# R151B.net
KiCad netlist of a schematic drawn in EAGLE
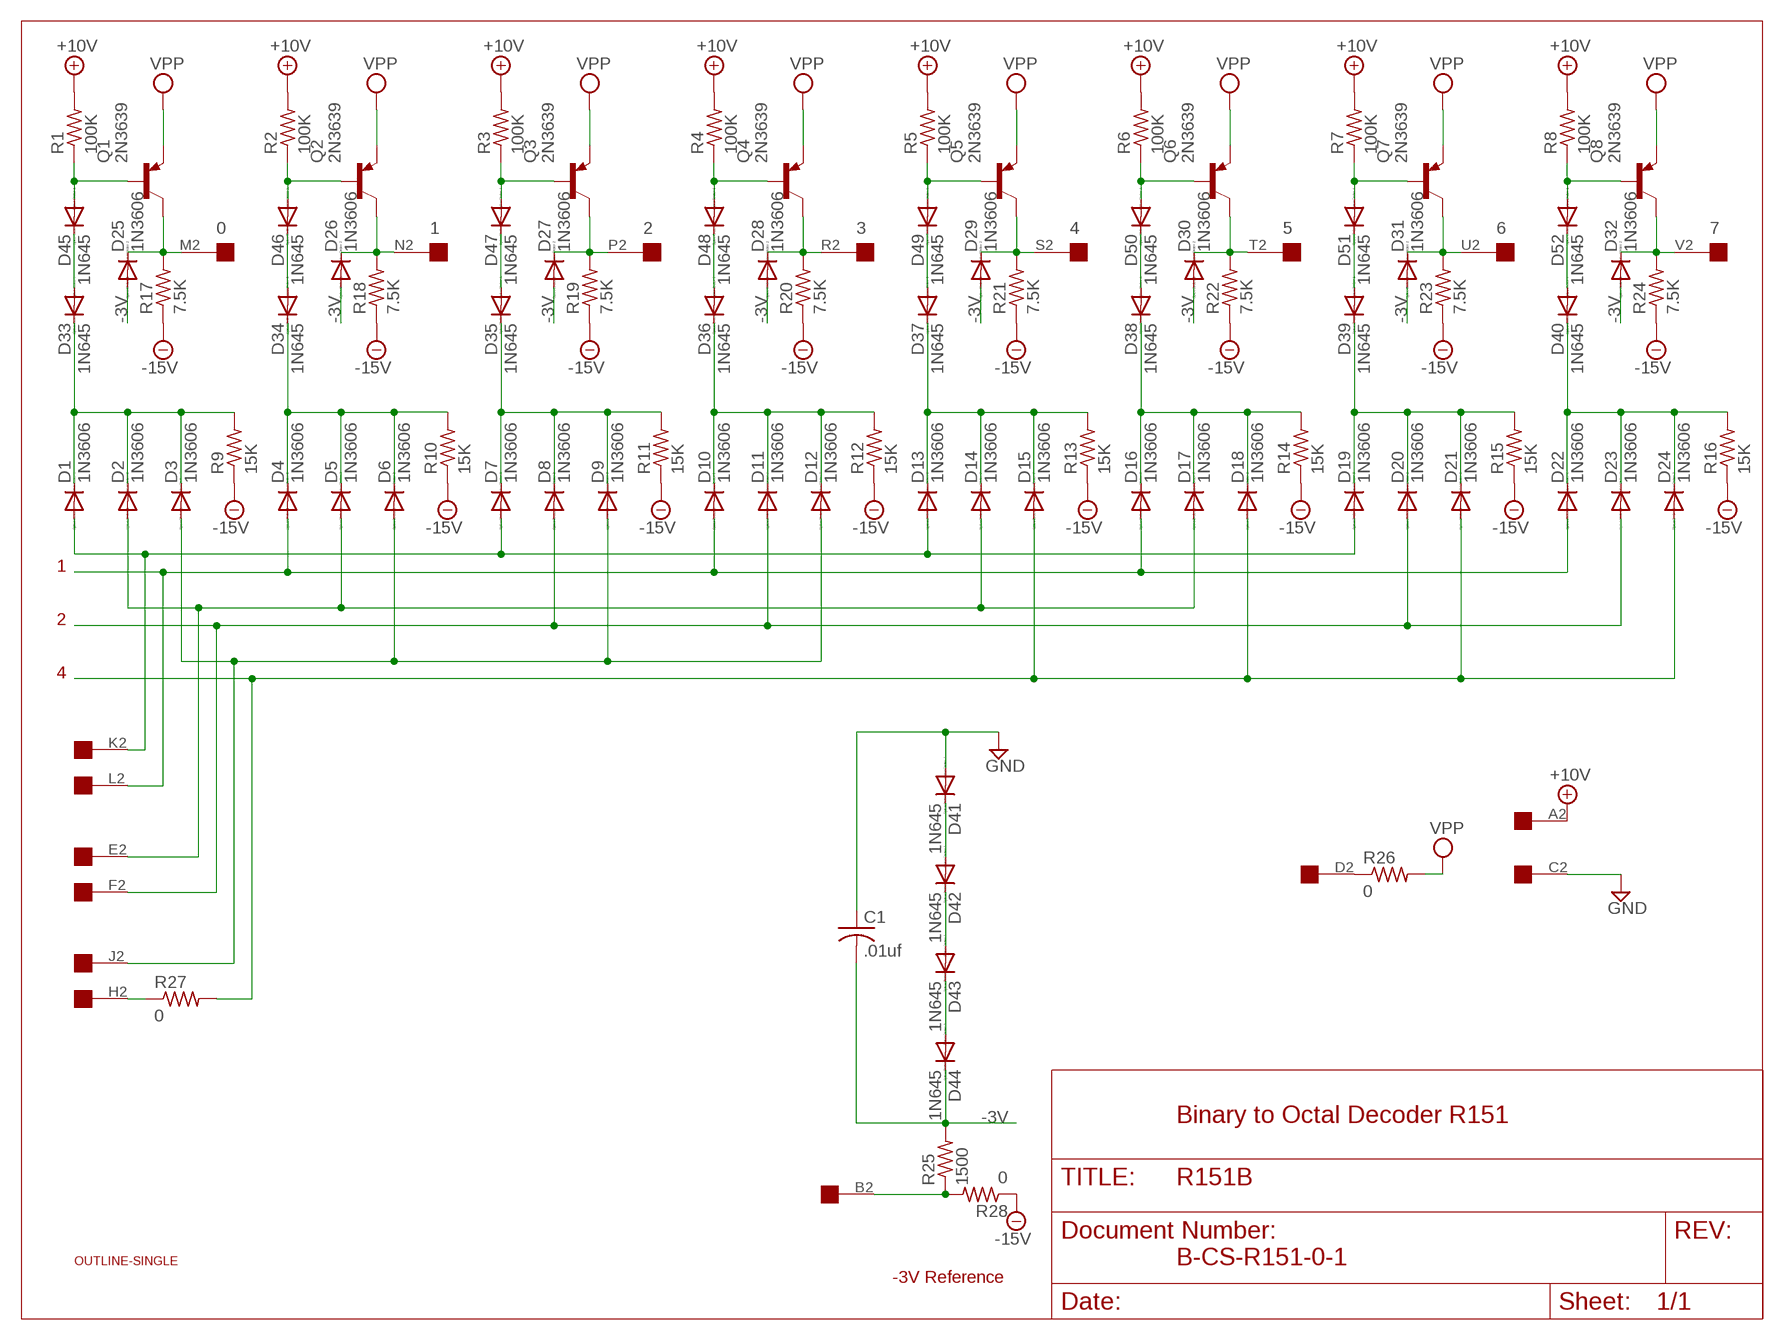
[diagram p0: schematic, sheet 1]

(export (version "E")
  (design (tool "Eeschema 10.0.6"))
  (components
    (comp (ref "C1")
      (value ".01uf")
      (footprint "eagle-import:C050-025X075")
      (libsource (lib "eagle-import") (part "C-US050-025X075"))
    )
    (comp (ref "D1")
      (value "1N3606")
      (footprint "eagle-import:DO35-10")
      (libsource (lib "eagle-import") (part "1N4148DO35-10"))
    )
    (comp (ref "D2")
      (value "1N3606")
      (footprint "eagle-import:DO35-10")
      (libsource (lib "eagle-import") (part "1N4148DO35-10"))
    )
    (comp (ref "D3")
      (value "1N3606")
      (footprint "eagle-import:DO35-10")
      (libsource (lib "eagle-import") (part "1N4148DO35-10"))
    )
    (comp (ref "D4")
      (value "1N3606")
      (footprint "eagle-import:DO35-10")
      (libsource (lib "eagle-import") (part "1N4148DO35-10"))
    )
    (comp (ref "D5")
      (value "1N3606")
      (footprint "eagle-import:DO35-10")
      (libsource (lib "eagle-import") (part "1N4148DO35-10"))
    )
    (comp (ref "D6")
      (value "1N3606")
      (footprint "eagle-import:DO35-10")
      (libsource (lib "eagle-import") (part "1N4148DO35-10"))
    )
    (comp (ref "D7")
      (value "1N3606")
      (footprint "eagle-import:DO35-10")
      (libsource (lib "eagle-import") (part "1N4148DO35-10"))
    )
    (comp (ref "D8")
      (value "1N3606")
      (footprint "eagle-import:DO35-10")
      (libsource (lib "eagle-import") (part "1N4148DO35-10"))
    )
    (comp (ref "D9")
      (value "1N3606")
      (footprint "eagle-import:DO35-10")
      (libsource (lib "eagle-import") (part "1N4148DO35-10"))
    )
    (comp (ref "D10")
      (value "1N3606")
      (footprint "eagle-import:DO35-10")
      (libsource (lib "eagle-import") (part "1N4148DO35-10"))
    )
    (comp (ref "D11")
      (value "1N3606")
      (footprint "eagle-import:DO35-10")
      (libsource (lib "eagle-import") (part "1N4148DO35-10"))
    )
    (comp (ref "D12")
      (value "1N3606")
      (footprint "eagle-import:DO35-10")
      (libsource (lib "eagle-import") (part "1N4148DO35-10"))
    )
    (comp (ref "D13")
      (value "1N3606")
      (footprint "eagle-import:DO35-10")
      (libsource (lib "eagle-import") (part "1N4148DO35-10"))
    )
    (comp (ref "D14")
      (value "1N3606")
      (footprint "eagle-import:DO35-10")
      (libsource (lib "eagle-import") (part "1N4148DO35-10"))
    )
    (comp (ref "D15")
      (value "1N3606")
      (footprint "eagle-import:DO35-10")
      (libsource (lib "eagle-import") (part "1N4148DO35-10"))
    )
    (comp (ref "D16")
      (value "1N3606")
      (footprint "eagle-import:DO35-10")
      (libsource (lib "eagle-import") (part "1N4148DO35-10"))
    )
    (comp (ref "D17")
      (value "1N3606")
      (footprint "eagle-import:DO35-10")
      (libsource (lib "eagle-import") (part "1N4148DO35-10"))
    )
    (comp (ref "D18")
      (value "1N3606")
      (footprint "eagle-import:DO35-10")
      (libsource (lib "eagle-import") (part "1N4148DO35-10"))
    )
    (comp (ref "D19")
      (value "1N3606")
      (footprint "eagle-import:DO35-10")
      (libsource (lib "eagle-import") (part "1N4148DO35-10"))
    )
    (comp (ref "D20")
      (value "1N3606")
      (footprint "eagle-import:DO35-10")
      (libsource (lib "eagle-import") (part "1N4148DO35-10"))
    )
    (comp (ref "D21")
      (value "1N3606")
      (footprint "eagle-import:DO35-10")
      (libsource (lib "eagle-import") (part "1N4148DO35-10"))
    )
    (comp (ref "D22")
      (value "1N3606")
      (footprint "eagle-import:DO35-10")
      (libsource (lib "eagle-import") (part "1N4148DO35-10"))
    )
    (comp (ref "D23")
      (value "1N3606")
      (footprint "eagle-import:DO35-10")
      (libsource (lib "eagle-import") (part "1N4148DO35-10"))
    )
    (comp (ref "D24")
      (value "1N3606")
      (footprint "eagle-import:DO35-10")
      (libsource (lib "eagle-import") (part "1N4148DO35-10"))
    )
    (comp (ref "D25")
      (value "1N3606")
      (footprint "eagle-import:DO35-10")
      (libsource (lib "eagle-import") (part "1N4148DO35-10"))
    )
    (comp (ref "D26")
      (value "1N3606")
      (footprint "eagle-import:DO35-10")
      (libsource (lib "eagle-import") (part "1N4148DO35-10"))
    )
    (comp (ref "D27")
      (value "1N3606")
      (footprint "eagle-import:DO35-10")
      (libsource (lib "eagle-import") (part "1N4148DO35-10"))
    )
    (comp (ref "D28")
      (value "1N3606")
      (footprint "eagle-import:DO35-10")
      (libsource (lib "eagle-import") (part "1N4148DO35-10"))
    )
    (comp (ref "D29")
      (value "1N3606")
      (footprint "eagle-import:DO35-10")
      (libsource (lib "eagle-import") (part "1N4148DO35-10"))
    )
    (comp (ref "D30")
      (value "1N3606")
      (footprint "eagle-import:DO35-10")
      (libsource (lib "eagle-import") (part "1N4148DO35-10"))
    )
    (comp (ref "D31")
      (value "1N3606")
      (footprint "eagle-import:DO35-10")
      (libsource (lib "eagle-import") (part "1N4148DO35-10"))
    )
    (comp (ref "D32")
      (value "1N3606")
      (footprint "eagle-import:DO35-10")
      (libsource (lib "eagle-import") (part "1N4148DO35-10"))
    )
    (comp (ref "D33")
      (value "1N645")
      (footprint "eagle-import:DO35-10")
      (libsource (lib "eagle-import") (part "1N4148DO35-10"))
    )
    (comp (ref "D34")
      (value "1N645")
      (footprint "eagle-import:DO35-10")
      (libsource (lib "eagle-import") (part "1N4148DO35-10"))
    )
    (comp (ref "D35")
      (value "1N645")
      (footprint "eagle-import:DO35-10")
      (libsource (lib "eagle-import") (part "1N4148DO35-10"))
    )
    (comp (ref "D36")
      (value "1N645")
      (footprint "eagle-import:DO35-10")
      (libsource (lib "eagle-import") (part "1N4148DO35-10"))
    )
    (comp (ref "D37")
      (value "1N645")
      (footprint "eagle-import:DO35-10")
      (libsource (lib "eagle-import") (part "1N4148DO35-10"))
    )
    (comp (ref "D38")
      (value "1N645")
      (footprint "eagle-import:DO35-10")
      (libsource (lib "eagle-import") (part "1N4148DO35-10"))
    )
    (comp (ref "D39")
      (value "1N645")
      (footprint "eagle-import:DO35-10")
      (libsource (lib "eagle-import") (part "1N4148DO35-10"))
    )
    (comp (ref "D40")
      (value "1N645")
      (footprint "eagle-import:DO35-10")
      (libsource (lib "eagle-import") (part "1N4148DO35-10"))
    )
    (comp (ref "D41")
      (value "1N645")
      (footprint "eagle-import:DO35-10")
      (libsource (lib "eagle-import") (part "1N4148DO35-10"))
    )
    (comp (ref "D42")
      (value "1N645")
      (footprint "eagle-import:DO35-10")
      (libsource (lib "eagle-import") (part "1N4148DO35-10"))
    )
    (comp (ref "D43")
      (value "1N645")
      (footprint "eagle-import:DO35-10")
      (libsource (lib "eagle-import") (part "1N4148DO35-10"))
    )
    (comp (ref "D44")
      (value "1N645")
      (footprint "eagle-import:DO35-10")
      (libsource (lib "eagle-import") (part "1N4148DO35-10"))
    )
    (comp (ref "D45")
      (value "1N645")
      (footprint "eagle-import:DO35-10")
      (libsource (lib "eagle-import") (part "1N4148DO35-10"))
    )
    (comp (ref "D46")
      (value "1N645")
      (footprint "eagle-import:DO35-10")
      (libsource (lib "eagle-import") (part "1N4148DO35-10"))
    )
    (comp (ref "D47")
      (value "1N645")
      (footprint "eagle-import:DO35-10")
      (libsource (lib "eagle-import") (part "1N4148DO35-10"))
    )
    (comp (ref "D48")
      (value "1N645")
      (footprint "eagle-import:DO35-10")
      (libsource (lib "eagle-import") (part "1N4148DO35-10"))
    )
    (comp (ref "D49")
      (value "1N645")
      (footprint "eagle-import:DO35-10")
      (libsource (lib "eagle-import") (part "1N4148DO35-10"))
    )
    (comp (ref "D50")
      (value "1N645")
      (footprint "eagle-import:DO35-10")
      (libsource (lib "eagle-import") (part "1N4148DO35-10"))
    )
    (comp (ref "D51")
      (value "1N645")
      (footprint "eagle-import:DO35-10")
      (libsource (lib "eagle-import") (part "1N4148DO35-10"))
    )
    (comp (ref "D52")
      (value "1N645")
      (footprint "eagle-import:DO35-10")
      (libsource (lib "eagle-import") (part "1N4148DO35-10"))
    )
    (comp (ref "Q1")
      (value "2N3639")
      (footprint "eagle-import:TO39")
      (libsource (lib "eagle-import") (part "2N3637"))
    )
    (comp (ref "Q2")
      (value "2N3639")
      (footprint "eagle-import:TO39")
      (libsource (lib "eagle-import") (part "2N3637"))
    )
    (comp (ref "Q3")
      (value "2N3639")
      (footprint "eagle-import:TO39")
      (libsource (lib "eagle-import") (part "2N3637"))
    )
    (comp (ref "Q4")
      (value "2N3639")
      (footprint "eagle-import:TO39")
      (libsource (lib "eagle-import") (part "2N3637"))
    )
    (comp (ref "Q5")
      (value "2N3639")
      (footprint "eagle-import:TO39")
      (libsource (lib "eagle-import") (part "2N3637"))
    )
    (comp (ref "Q6")
      (value "2N3639")
      (footprint "eagle-import:TO39")
      (libsource (lib "eagle-import") (part "2N3637"))
    )
    (comp (ref "Q7")
      (value "2N3639")
      (footprint "eagle-import:TO39")
      (libsource (lib "eagle-import") (part "2N3637"))
    )
    (comp (ref "Q8")
      (value "2N3639")
      (footprint "eagle-import:TO39")
      (libsource (lib "eagle-import") (part "2N3637"))
    )
    (comp (ref "R1")
      (value "100K")
      (footprint "eagle-import:0207_10")
      (libsource (lib "eagle-import") (part "R-US_0207/10"))
    )
    (comp (ref "R2")
      (value "100K")
      (footprint "eagle-import:0207_10")
      (libsource (lib "eagle-import") (part "R-US_0207/10"))
    )
    (comp (ref "R3")
      (value "100K")
      (footprint "eagle-import:0207_10")
      (libsource (lib "eagle-import") (part "R-US_0207/10"))
    )
    (comp (ref "R4")
      (value "100K")
      (footprint "eagle-import:0207_10")
      (libsource (lib "eagle-import") (part "R-US_0207/10"))
    )
    (comp (ref "R5")
      (value "100K")
      (footprint "eagle-import:0207_10")
      (libsource (lib "eagle-import") (part "R-US_0207/10"))
    )
    (comp (ref "R6")
      (value "100K")
      (footprint "eagle-import:0207_10")
      (libsource (lib "eagle-import") (part "R-US_0207/10"))
    )
    (comp (ref "R7")
      (value "100K")
      (footprint "eagle-import:0207_10")
      (libsource (lib "eagle-import") (part "R-US_0207/10"))
    )
    (comp (ref "R8")
      (value "100K")
      (footprint "eagle-import:0207_10")
      (libsource (lib "eagle-import") (part "R-US_0207/10"))
    )
    (comp (ref "R9")
      (value "15K")
      (footprint "eagle-import:0207_10")
      (libsource (lib "eagle-import") (part "R-US_0207/10"))
    )
    (comp (ref "R10")
      (value "15K")
      (footprint "eagle-import:0207_10")
      (libsource (lib "eagle-import") (part "R-US_0207/10"))
    )
    (comp (ref "R11")
      (value "15K")
      (footprint "eagle-import:0207_10")
      (libsource (lib "eagle-import") (part "R-US_0207/10"))
    )
    (comp (ref "R12")
      (value "15K")
      (footprint "eagle-import:0207_10")
      (libsource (lib "eagle-import") (part "R-US_0207/10"))
    )
    (comp (ref "R13")
      (value "15K")
      (footprint "eagle-import:0207_10")
      (libsource (lib "eagle-import") (part "R-US_0207/10"))
    )
    (comp (ref "R14")
      (value "15K")
      (footprint "eagle-import:0207_10")
      (libsource (lib "eagle-import") (part "R-US_0207/10"))
    )
    (comp (ref "R15")
      (value "15K")
      (footprint "eagle-import:0207_10")
      (libsource (lib "eagle-import") (part "R-US_0207/10"))
    )
    (comp (ref "R16")
      (value "15K")
      (footprint "eagle-import:0207_10")
      (libsource (lib "eagle-import") (part "R-US_0207/10"))
    )
    (comp (ref "R17")
      (value "7.5K")
      (footprint "eagle-import:0207_10")
      (libsource (lib "eagle-import") (part "R-US_0207/10"))
    )
    (comp (ref "R18")
      (value "7.5K")
      (footprint "eagle-import:0207_10")
      (libsource (lib "eagle-import") (part "R-US_0207/10"))
    )
    (comp (ref "R19")
      (value "7.5K")
      (footprint "eagle-import:0207_10")
      (libsource (lib "eagle-import") (part "R-US_0207/10"))
    )
    (comp (ref "R20")
      (value "7.5K")
      (footprint "eagle-import:0207_10")
      (libsource (lib "eagle-import") (part "R-US_0207/10"))
    )
    (comp (ref "R21")
      (value "7.5K")
      (footprint "eagle-import:0207_10")
      (libsource (lib "eagle-import") (part "R-US_0207/10"))
    )
    (comp (ref "R22")
      (value "7.5K")
      (footprint "eagle-import:0207_10")
      (libsource (lib "eagle-import") (part "R-US_0207/10"))
    )
    (comp (ref "R23")
      (value "7.5K")
      (footprint "eagle-import:0207_10")
      (libsource (lib "eagle-import") (part "R-US_0207/10"))
    )
    (comp (ref "R24")
      (value "7.5K")
      (footprint "eagle-import:0207_10")
      (libsource (lib "eagle-import") (part "R-US_0207/10"))
    )
    (comp (ref "R25")
      (value "1500")
      (footprint "eagle-import:0207_10")
      (libsource (lib "eagle-import") (part "R-US_0207/10"))
    )
    (comp (ref "R26")
      (value "0")
      (footprint "eagle-import:0207_10")
      (libsource (lib "eagle-import") (part "R-US_0207/10"))
    )
    (comp (ref "R27")
      (value "0")
      (footprint "eagle-import:0207_10")
      (libsource (lib "eagle-import") (part "R-US_0207/10"))
    )
    (comp (ref "R28")
      (value "0")
      (footprint "eagle-import:0207_10")
      (libsource (lib "eagle-import") (part "R-US_0207/10"))
    )
    (comp (ref "U$1")
      (value "OUTLINE-SINGLE")
      (footprint "eagle-import:SINGLE")
      (libsource (lib "eagle-import") (part "OUTLINE-SINGLE"))
    )
    (comp (ref "U$2")
      (value "EDGE-1")
      (footprint "eagle-import:EDGE-CON1")
      (libsource (lib "eagle-import") (part "EDGE-1"))
    )
  )
  (nets
    (net (code "1") (name "+10V") (class "Default")
      (node (ref "R1") (pin "2") (pinfunction "2_2") (pintype "passive"))
      (node (ref "R2") (pin "2") (pinfunction "2_2") (pintype "passive"))
      (node (ref "R3") (pin "2") (pinfunction "2_2") (pintype "passive"))
      (node (ref "R4") (pin "2") (pinfunction "2_2") (pintype "passive"))
      (node (ref "R5") (pin "2") (pinfunction "2_2") (pintype "passive"))
      (node (ref "R6") (pin "2") (pinfunction "2_2") (pintype "passive"))
      (node (ref "R7") (pin "2") (pinfunction "2_2") (pintype "passive"))
      (node (ref "R8") (pin "2") (pinfunction "2_2") (pintype "passive"))
      (node (ref "U$2") (pin "A2") (pinfunction "1_A2") (pintype "bidirectional"))
    )
    (net (code "2") (name "-15V") (class "Default")
      (node (ref "R10") (pin "1") (pinfunction "1_1") (pintype "passive"))
      (node (ref "R11") (pin "1") (pinfunction "1_1") (pintype "passive"))
      (node (ref "R12") (pin "1") (pinfunction "1_1") (pintype "passive"))
      (node (ref "R13") (pin "1") (pinfunction "1_1") (pintype "passive"))
      (node (ref "R14") (pin "1") (pinfunction "1_1") (pintype "passive"))
      (node (ref "R15") (pin "1") (pinfunction "1_1") (pintype "passive"))
      (node (ref "R16") (pin "1") (pinfunction "1_1") (pintype "passive"))
      (node (ref "R17") (pin "1") (pinfunction "1_1") (pintype "passive"))
      (node (ref "R18") (pin "1") (pinfunction "1_1") (pintype "passive"))
      (node (ref "R19") (pin "1") (pinfunction "1_1") (pintype "passive"))
      (node (ref "R20") (pin "1") (pinfunction "1_1") (pintype "passive"))
      (node (ref "R21") (pin "1") (pinfunction "1_1") (pintype "passive"))
      (node (ref "R22") (pin "1") (pinfunction "1_1") (pintype "passive"))
      (node (ref "R23") (pin "1") (pinfunction "1_1") (pintype "passive"))
      (node (ref "R24") (pin "1") (pinfunction "1_1") (pintype "passive"))
      (node (ref "R28") (pin "1") (pinfunction "1_1") (pintype "passive"))
      (node (ref "R9") (pin "1") (pinfunction "1_1") (pintype "passive"))
    )
    (net (code "3") (name "/-3V") (class "Default")
      (node (ref "C1") (pin "2") (pinfunction "2_2") (pintype "passive"))
      (node (ref "D25") (pin "A") (pinfunction "A_A") (pintype "passive"))
      (node (ref "D26") (pin "A") (pinfunction "A_A") (pintype "passive"))
      (node (ref "D27") (pin "A") (pinfunction "A_A") (pintype "passive"))
      (node (ref "D28") (pin "A") (pinfunction "A_A") (pintype "passive"))
      (node (ref "D29") (pin "A") (pinfunction "A_A") (pintype "passive"))
      (node (ref "D30") (pin "A") (pinfunction "A_A") (pintype "passive"))
      (node (ref "D31") (pin "A") (pinfunction "A_A") (pintype "passive"))
      (node (ref "D32") (pin "A") (pinfunction "A_A") (pintype "passive"))
      (node (ref "D44") (pin "C") (pinfunction "C_C") (pintype "passive"))
      (node (ref "R25") (pin "2") (pinfunction "2_2") (pintype "passive"))
    )
    (net (code "4") (name "/0") (class "Default")
      (node (ref "D25") (pin "C") (pinfunction "C_C") (pintype "passive"))
      (node (ref "Q1") (pin "3") (pinfunction "C_3") (pintype "passive"))
      (node (ref "R17") (pin "2") (pinfunction "2_2") (pintype "passive"))
      (node (ref "U$2") (pin "M2") (pinfunction "1_M2") (pintype "bidirectional"))
    )
    (net (code "5") (name "/1") (class "Default")
      (node (ref "D26") (pin "C") (pinfunction "C_C") (pintype "passive"))
      (node (ref "Q2") (pin "3") (pinfunction "C_3") (pintype "passive"))
      (node (ref "R18") (pin "2") (pinfunction "2_2") (pintype "passive"))
      (node (ref "U$2") (pin "N2") (pinfunction "1_N2") (pintype "bidirectional"))
    )
    (net (code "6") (name "/2") (class "Default")
      (node (ref "D27") (pin "C") (pinfunction "C_C") (pintype "passive"))
      (node (ref "Q3") (pin "3") (pinfunction "C_3") (pintype "passive"))
      (node (ref "R19") (pin "2") (pinfunction "2_2") (pintype "passive"))
      (node (ref "U$2") (pin "P2") (pinfunction "1_P2") (pintype "bidirectional"))
    )
    (net (code "7") (name "/3") (class "Default")
      (node (ref "D28") (pin "C") (pinfunction "C_C") (pintype "passive"))
      (node (ref "Q4") (pin "3") (pinfunction "C_3") (pintype "passive"))
      (node (ref "R20") (pin "2") (pinfunction "2_2") (pintype "passive"))
      (node (ref "U$2") (pin "R2") (pinfunction "1_R2") (pintype "bidirectional"))
    )
    (net (code "8") (name "/4") (class "Default")
      (node (ref "D29") (pin "C") (pinfunction "C_C") (pintype "passive"))
      (node (ref "Q5") (pin "3") (pinfunction "C_3") (pintype "passive"))
      (node (ref "R21") (pin "2") (pinfunction "2_2") (pintype "passive"))
      (node (ref "U$2") (pin "S2") (pinfunction "1_S2") (pintype "bidirectional"))
    )
    (net (code "9") (name "/5") (class "Default")
      (node (ref "D30") (pin "C") (pinfunction "C_C") (pintype "passive"))
      (node (ref "Q6") (pin "3") (pinfunction "C_3") (pintype "passive"))
      (node (ref "R22") (pin "2") (pinfunction "2_2") (pintype "passive"))
      (node (ref "U$2") (pin "T2") (pinfunction "1_T2") (pintype "bidirectional"))
    )
    (net (code "10") (name "/6") (class "Default")
      (node (ref "D31") (pin "C") (pinfunction "C_C") (pintype "passive"))
      (node (ref "Q7") (pin "3") (pinfunction "C_3") (pintype "passive"))
      (node (ref "R23") (pin "2") (pinfunction "2_2") (pintype "passive"))
      (node (ref "U$2") (pin "U2") (pinfunction "1_U2") (pintype "bidirectional"))
    )
    (net (code "11") (name "/7") (class "Default")
      (node (ref "D32") (pin "C") (pinfunction "C_C") (pintype "passive"))
      (node (ref "Q8") (pin "3") (pinfunction "C_3") (pintype "passive"))
      (node (ref "R24") (pin "2") (pinfunction "2_2") (pintype "passive"))
      (node (ref "U$2") (pin "V2") (pinfunction "1_V2") (pintype "bidirectional"))
    )
    (net (code "12") (name "GND") (class "Default")
      (node (ref "C1") (pin "1") (pinfunction "1_1") (pintype "passive"))
      (node (ref "D41") (pin "A") (pinfunction "A_A") (pintype "passive"))
      (node (ref "U$2") (pin "C2") (pinfunction "1_C2") (pintype "bidirectional"))
    )
    (net (code "13") (name "Net-(D1-PadC)") (class "Default")
      (node (ref "D1") (pin "C") (pinfunction "C_C") (pintype "passive"))
      (node (ref "D2") (pin "C") (pinfunction "C_C") (pintype "passive"))
      (node (ref "D3") (pin "C") (pinfunction "C_C") (pintype "passive"))
      (node (ref "D33") (pin "C") (pinfunction "C_C") (pintype "passive"))
      (node (ref "R9") (pin "2") (pinfunction "2_2") (pintype "passive"))
    )
    (net (code "14") (name "Net-(D10-PadC)") (class "Default")
      (node (ref "D10") (pin "C") (pinfunction "C_C") (pintype "passive"))
      (node (ref "D11") (pin "C") (pinfunction "C_C") (pintype "passive"))
      (node (ref "D12") (pin "C") (pinfunction "C_C") (pintype "passive"))
      (node (ref "D36") (pin "C") (pinfunction "C_C") (pintype "passive"))
      (node (ref "R12") (pin "2") (pinfunction "2_2") (pintype "passive"))
    )
    (net (code "15") (name "Net-(D13-PadC)") (class "Default")
      (node (ref "D13") (pin "C") (pinfunction "C_C") (pintype "passive"))
      (node (ref "D14") (pin "C") (pinfunction "C_C") (pintype "passive"))
      (node (ref "D15") (pin "C") (pinfunction "C_C") (pintype "passive"))
      (node (ref "D37") (pin "C") (pinfunction "C_C") (pintype "passive"))
      (node (ref "R13") (pin "2") (pinfunction "2_2") (pintype "passive"))
    )
    (net (code "16") (name "Net-(D15-PadA)") (class "Default")
      (node (ref "D15") (pin "A") (pinfunction "A_A") (pintype "passive"))
      (node (ref "D18") (pin "A") (pinfunction "A_A") (pintype "passive"))
      (node (ref "D21") (pin "A") (pinfunction "A_A") (pintype "passive"))
      (node (ref "D24") (pin "A") (pinfunction "A_A") (pintype "passive"))
      (node (ref "R27") (pin "2") (pinfunction "2_2") (pintype "passive"))
    )
    (net (code "17") (name "Net-(D16-PadC)") (class "Default")
      (node (ref "D16") (pin "C") (pinfunction "C_C") (pintype "passive"))
      (node (ref "D17") (pin "C") (pinfunction "C_C") (pintype "passive"))
      (node (ref "D18") (pin "C") (pinfunction "C_C") (pintype "passive"))
      (node (ref "D38") (pin "C") (pinfunction "C_C") (pintype "passive"))
      (node (ref "R14") (pin "2") (pinfunction "2_2") (pintype "passive"))
    )
    (net (code "18") (name "Net-(D19-PadC)") (class "Default")
      (node (ref "D19") (pin "C") (pinfunction "C_C") (pintype "passive"))
      (node (ref "D20") (pin "C") (pinfunction "C_C") (pintype "passive"))
      (node (ref "D21") (pin "C") (pinfunction "C_C") (pintype "passive"))
      (node (ref "D39") (pin "C") (pinfunction "C_C") (pintype "passive"))
      (node (ref "R15") (pin "2") (pinfunction "2_2") (pintype "passive"))
    )
    (net (code "19") (name "Net-(D22-PadC)") (class "Default")
      (node (ref "D22") (pin "C") (pinfunction "C_C") (pintype "passive"))
      (node (ref "D23") (pin "C") (pinfunction "C_C") (pintype "passive"))
      (node (ref "D24") (pin "C") (pinfunction "C_C") (pintype "passive"))
      (node (ref "D40") (pin "C") (pinfunction "C_C") (pintype "passive"))
      (node (ref "R16") (pin "2") (pinfunction "2_2") (pintype "passive"))
    )
    (net (code "20") (name "Net-(D33-PadA)") (class "Default")
      (node (ref "D33") (pin "A") (pinfunction "A_A") (pintype "passive"))
      (node (ref "D45") (pin "C") (pinfunction "C_C") (pintype "passive"))
    )
    (net (code "21") (name "Net-(D34-PadA)") (class "Default")
      (node (ref "D34") (pin "A") (pinfunction "A_A") (pintype "passive"))
      (node (ref "D46") (pin "C") (pinfunction "C_C") (pintype "passive"))
    )
    (net (code "22") (name "Net-(D34-PadC)") (class "Default")
      (node (ref "D34") (pin "C") (pinfunction "C_C") (pintype "passive"))
      (node (ref "D4") (pin "C") (pinfunction "C_C") (pintype "passive"))
      (node (ref "D5") (pin "C") (pinfunction "C_C") (pintype "passive"))
      (node (ref "D6") (pin "C") (pinfunction "C_C") (pintype "passive"))
      (node (ref "R10") (pin "2") (pinfunction "2_2") (pintype "passive"))
    )
    (net (code "23") (name "Net-(D35-PadA)") (class "Default")
      (node (ref "D35") (pin "A") (pinfunction "A_A") (pintype "passive"))
      (node (ref "D47") (pin "C") (pinfunction "C_C") (pintype "passive"))
    )
    (net (code "24") (name "Net-(D35-PadC)") (class "Default")
      (node (ref "D35") (pin "C") (pinfunction "C_C") (pintype "passive"))
      (node (ref "D7") (pin "C") (pinfunction "C_C") (pintype "passive"))
      (node (ref "D8") (pin "C") (pinfunction "C_C") (pintype "passive"))
      (node (ref "D9") (pin "C") (pinfunction "C_C") (pintype "passive"))
      (node (ref "R11") (pin "2") (pinfunction "2_2") (pintype "passive"))
    )
    (net (code "25") (name "Net-(D36-PadA)") (class "Default")
      (node (ref "D36") (pin "A") (pinfunction "A_A") (pintype "passive"))
      (node (ref "D48") (pin "C") (pinfunction "C_C") (pintype "passive"))
    )
    (net (code "26") (name "Net-(D37-PadA)") (class "Default")
      (node (ref "D37") (pin "A") (pinfunction "A_A") (pintype "passive"))
      (node (ref "D49") (pin "C") (pinfunction "C_C") (pintype "passive"))
    )
    (net (code "27") (name "Net-(D38-PadA)") (class "Default")
      (node (ref "D38") (pin "A") (pinfunction "A_A") (pintype "passive"))
      (node (ref "D50") (pin "C") (pinfunction "C_C") (pintype "passive"))
    )
    (net (code "28") (name "Net-(D39-PadA)") (class "Default")
      (node (ref "D39") (pin "A") (pinfunction "A_A") (pintype "passive"))
      (node (ref "D51") (pin "C") (pinfunction "C_C") (pintype "passive"))
    )
    (net (code "29") (name "Net-(D40-PadA)") (class "Default")
      (node (ref "D40") (pin "A") (pinfunction "A_A") (pintype "passive"))
      (node (ref "D52") (pin "C") (pinfunction "C_C") (pintype "passive"))
    )
    (net (code "30") (name "Net-(D41-PadC)") (class "Default")
      (node (ref "D41") (pin "C") (pinfunction "C_C") (pintype "passive"))
      (node (ref "D42") (pin "A") (pinfunction "A_A") (pintype "passive"))
    )
    (net (code "31") (name "Net-(D42-PadC)") (class "Default")
      (node (ref "D42") (pin "C") (pinfunction "C_C") (pintype "passive"))
      (node (ref "D43") (pin "A") (pinfunction "A_A") (pintype "passive"))
    )
    (net (code "32") (name "Net-(D43-PadC)") (class "Default")
      (node (ref "D43") (pin "C") (pinfunction "C_C") (pintype "passive"))
      (node (ref "D44") (pin "A") (pinfunction "A_A") (pintype "passive"))
    )
    (net (code "33") (name "Net-(Q1-B)") (class "Default")
      (node (ref "D45") (pin "A") (pinfunction "A_A") (pintype "passive"))
      (node (ref "Q1") (pin "2") (pinfunction "B_2") (pintype "passive"))
      (node (ref "R1") (pin "1") (pinfunction "1_1") (pintype "passive"))
    )
    (net (code "34") (name "Net-(Q2-B)") (class "Default")
      (node (ref "D46") (pin "A") (pinfunction "A_A") (pintype "passive"))
      (node (ref "Q2") (pin "2") (pinfunction "B_2") (pintype "passive"))
      (node (ref "R2") (pin "1") (pinfunction "1_1") (pintype "passive"))
    )
    (net (code "35") (name "Net-(Q3-B)") (class "Default")
      (node (ref "D47") (pin "A") (pinfunction "A_A") (pintype "passive"))
      (node (ref "Q3") (pin "2") (pinfunction "B_2") (pintype "passive"))
      (node (ref "R3") (pin "1") (pinfunction "1_1") (pintype "passive"))
    )
    (net (code "36") (name "Net-(Q4-B)") (class "Default")
      (node (ref "D48") (pin "A") (pinfunction "A_A") (pintype "passive"))
      (node (ref "Q4") (pin "2") (pinfunction "B_2") (pintype "passive"))
      (node (ref "R4") (pin "1") (pinfunction "1_1") (pintype "passive"))
    )
    (net (code "37") (name "Net-(Q5-B)") (class "Default")
      (node (ref "D49") (pin "A") (pinfunction "A_A") (pintype "passive"))
      (node (ref "Q5") (pin "2") (pinfunction "B_2") (pintype "passive"))
      (node (ref "R5") (pin "1") (pinfunction "1_1") (pintype "passive"))
    )
    (net (code "38") (name "Net-(Q6-B)") (class "Default")
      (node (ref "D50") (pin "A") (pinfunction "A_A") (pintype "passive"))
      (node (ref "Q6") (pin "2") (pinfunction "B_2") (pintype "passive"))
      (node (ref "R6") (pin "1") (pinfunction "1_1") (pintype "passive"))
    )
    (net (code "39") (name "Net-(Q7-B)") (class "Default")
      (node (ref "D51") (pin "A") (pinfunction "A_A") (pintype "passive"))
      (node (ref "Q7") (pin "2") (pinfunction "B_2") (pintype "passive"))
      (node (ref "R7") (pin "1") (pinfunction "1_1") (pintype "passive"))
    )
    (net (code "40") (name "Net-(Q8-B)") (class "Default")
      (node (ref "D52") (pin "A") (pinfunction "A_A") (pintype "passive"))
      (node (ref "Q8") (pin "2") (pinfunction "B_2") (pintype "passive"))
      (node (ref "R8") (pin "1") (pinfunction "1_1") (pintype "passive"))
    )
    (net (code "41") (name "Net-(U$2B-1)") (class "Default")
      (node (ref "R25") (pin "1") (pinfunction "1_1") (pintype "passive"))
      (node (ref "R28") (pin "2") (pinfunction "2_2") (pintype "passive"))
      (node (ref "U$2") (pin "B2") (pinfunction "1_B2") (pintype "bidirectional"))
    )
    (net (code "42") (name "Net-(U$2D-1)") (class "Default")
      (node (ref "R26") (pin "1") (pinfunction "1_1") (pintype "passive"))
      (node (ref "U$2") (pin "D2") (pinfunction "1_D2") (pintype "bidirectional"))
    )
    (net (code "43") (name "Net-(U$2E-1)") (class "Default")
      (node (ref "D14") (pin "A") (pinfunction "A_A") (pintype "passive"))
      (node (ref "D17") (pin "A") (pinfunction "A_A") (pintype "passive"))
      (node (ref "D2") (pin "A") (pinfunction "A_A") (pintype "passive"))
      (node (ref "D5") (pin "A") (pinfunction "A_A") (pintype "passive"))
      (node (ref "U$2") (pin "E2") (pinfunction "1_E2") (pintype "bidirectional"))
    )
    (net (code "44") (name "Net-(U$2F-1)") (class "Default")
      (node (ref "D11") (pin "A") (pinfunction "A_A") (pintype "passive"))
      (node (ref "D20") (pin "A") (pinfunction "A_A") (pintype "passive"))
      (node (ref "D23") (pin "A") (pinfunction "A_A") (pintype "passive"))
      (node (ref "D8") (pin "A") (pinfunction "A_A") (pintype "passive"))
      (node (ref "U$2") (pin "F2") (pinfunction "1_F2") (pintype "bidirectional"))
    )
    (net (code "45") (name "Net-(U$2G-1)") (class "Default")
      (node (ref "R27") (pin "1") (pinfunction "1_1") (pintype "passive"))
      (node (ref "U$2") (pin "H2") (pinfunction "1_H2") (pintype "bidirectional"))
    )
    (net (code "46") (name "Net-(U$2H-1)") (class "Default")
      (node (ref "D12") (pin "A") (pinfunction "A_A") (pintype "passive"))
      (node (ref "D3") (pin "A") (pinfunction "A_A") (pintype "passive"))
      (node (ref "D6") (pin "A") (pinfunction "A_A") (pintype "passive"))
      (node (ref "D9") (pin "A") (pinfunction "A_A") (pintype "passive"))
      (node (ref "U$2") (pin "J2") (pinfunction "1_J2") (pintype "bidirectional"))
    )
    (net (code "47") (name "Net-(U$2I-1)") (class "Default")
      (node (ref "D1") (pin "A") (pinfunction "A_A") (pintype "passive"))
      (node (ref "D13") (pin "A") (pinfunction "A_A") (pintype "passive"))
      (node (ref "D19") (pin "A") (pinfunction "A_A") (pintype "passive"))
      (node (ref "D7") (pin "A") (pinfunction "A_A") (pintype "passive"))
      (node (ref "U$2") (pin "K2") (pinfunction "1_K2") (pintype "bidirectional"))
    )
    (net (code "48") (name "Net-(U$2J-1)") (class "Default")
      (node (ref "D10") (pin "A") (pinfunction "A_A") (pintype "passive"))
      (node (ref "D16") (pin "A") (pinfunction "A_A") (pintype "passive"))
      (node (ref "D22") (pin "A") (pinfunction "A_A") (pintype "passive"))
      (node (ref "D4") (pin "A") (pinfunction "A_A") (pintype "passive"))
      (node (ref "U$2") (pin "L2") (pinfunction "1_L2") (pintype "bidirectional"))
    )
    (net (code "49") (name "VPP") (class "Default")
      (node (ref "Q1") (pin "1") (pinfunction "E_1") (pintype "passive"))
      (node (ref "Q2") (pin "1") (pinfunction "E_1") (pintype "passive"))
      (node (ref "Q3") (pin "1") (pinfunction "E_1") (pintype "passive"))
      (node (ref "Q4") (pin "1") (pinfunction "E_1") (pintype "passive"))
      (node (ref "Q5") (pin "1") (pinfunction "E_1") (pintype "passive"))
      (node (ref "Q6") (pin "1") (pinfunction "E_1") (pintype "passive"))
      (node (ref "Q7") (pin "1") (pinfunction "E_1") (pintype "passive"))
      (node (ref "Q8") (pin "1") (pinfunction "E_1") (pintype "passive"))
      (node (ref "R26") (pin "2") (pinfunction "2_2") (pintype "passive"))
    )
  )
)
